# clock.net
KiCad netlist of a schematic drawn in Altium Designer
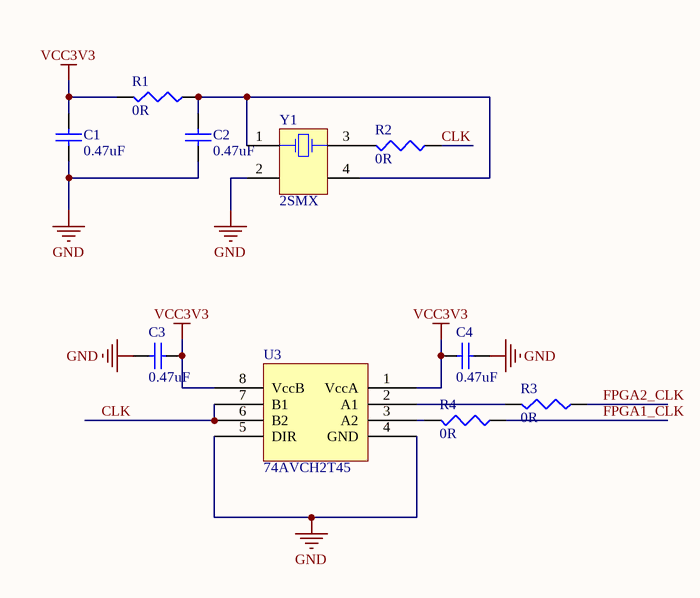
[diagram p0: clock.SchDoc]

(export (version "E")
  (design (tool "Eeschema 10.0.6"))
  (components
    (comp (ref "C1")
      (value "0.47uF")
      (footprint "CAPC1005N")
      (description "Capacitor (Semiconductor SIM Model)")
      (fields (field (name "PUBLISHER") "Altium Limited"))
      (libsource (lib "Miscellaneous Devices") (part "Cap Semi"))
    )
    (comp (ref "C2")
      (value "0.47uF")
      (footprint "CAPC1005N")
      (description "Capacitor (Semiconductor SIM Model)")
      (fields (field (name "PUBLISHER") "Altium Limited"))
      (libsource (lib "Miscellaneous Devices") (part "Cap Semi"))
    )
    (comp (ref "C3")
      (value "0.47uF")
      (footprint "CAPC1005N")
      (description "Capacitor (Semiconductor SIM Model)")
      (fields (field (name "PUBLISHER") "Altium Limited"))
      (libsource (lib "Miscellaneous Devices") (part "Cap Semi"))
    )
    (comp (ref "C4")
      (value "0.47uF")
      (footprint "CAPC1005N")
      (description "Capacitor (Semiconductor SIM Model)")
      (fields (field (name "PUBLISHER") "Altium Limited"))
      (libsource (lib "Miscellaneous Devices") (part "Cap Semi"))
    )
    (comp (ref "R1")
      (value "0R")
      (footprint "RESC1005N")
      (description "Resistor")
      (fields (field (name "PUBLISHER") "Altium Limited"))
      (libsource (lib "Miscellaneous Devices") (part "Res3"))
    )
    (comp (ref "R2")
      (value "0R")
      (footprint "RESC1005N")
      (description "Resistor")
      (fields (field (name "PUBLISHER") "Altium Limited"))
      (libsource (lib "Miscellaneous Devices") (part "Res3"))
    )
    (comp (ref "R3")
      (value "0R")
      (footprint "RESC1005N")
      (description "Resistor")
      (fields (field (name "PUBLISHER") "Altium Limited"))
      (libsource (lib "Miscellaneous Devices") (part "Res3"))
    )
    (comp (ref "R4")
      (value "0R")
      (footprint "RESC1005N")
      (description "Resistor")
      (fields (field (name "PUBLISHER") "Altium Limited"))
      (libsource (lib "Miscellaneous Devices") (part "Res3"))
    )
    (comp (ref "U3") (value "74AVCH2T45") (footprint "SOT765-1") (libsource (lib "S6") (part "74AVCH2T45")))
    (comp (ref "Y1")
      (value "2SMX")
      (footprint "SMX2")
      (description "Surface Mount Quartz Crystal")
      (fields (field (name "PUBLISHER") "Altium Limited"))
      (libsource (lib "C-MAC Crystal Oscillator") (part "2SMX"))
    )
  )
  (nets
    (net (code "1") (name "/CLK") (class "Default")
      (node (ref "R2") (pin "1") (pinfunction "1_1") (pintype "passive"))
      (node (ref "U3") (pin "6") (pinfunction "B2_6") (pintype "passive"))
      (node (ref "U3") (pin "7") (pinfunction "B1_7") (pintype "passive"))
    )
    (net (code "2") (name "/FPGA1_CLK") (class "Default")
      (node (ref "R4") (pin "1") (pinfunction "1_1") (pintype "passive"))
    )
    (net (code "3") (name "/FPGA2_CLK") (class "Default")
      (node (ref "R3") (pin "1") (pinfunction "1_1") (pintype "passive"))
    )
    (net (code "4") (name "GND") (class "Default")
      (node (ref "C1") (pin "1") (pinfunction "1_1") (pintype "passive"))
      (node (ref "C2") (pin "1") (pinfunction "1_1") (pintype "passive"))
      (node (ref "C3") (pin "2") (pinfunction "2_2") (pintype "passive"))
      (node (ref "C4") (pin "1") (pinfunction "1_1") (pintype "passive"))
      (node (ref "U3") (pin "4") (pinfunction "GND_4") (pintype "passive"))
      (node (ref "U3") (pin "5") (pinfunction "DIR_5") (pintype "passive"))
      (node (ref "Y1") (pin "2") (pinfunction "NC_2") (pintype "passive"))
    )
    (net (code "5") (name "Net-(U3-A1)") (class "Default")
      (node (ref "R3") (pin "2") (pinfunction "2_2") (pintype "passive"))
      (node (ref "U3") (pin "2") (pinfunction "A1_2") (pintype "passive"))
    )
    (net (code "6") (name "Net-(U3-A2)") (class "Default")
      (node (ref "R4") (pin "2") (pinfunction "2_2") (pintype "passive"))
      (node (ref "U3") (pin "3") (pinfunction "A2_3") (pintype "passive"))
    )
    (net (code "7") (name "Net-(Y1-OSC1)") (class "Default")
      (node (ref "C2") (pin "2") (pinfunction "2_2") (pintype "passive"))
      (node (ref "R1") (pin "1") (pinfunction "1_1") (pintype "passive"))
      (node (ref "Y1") (pin "1") (pinfunction "OSC1_1") (pintype "passive"))
      (node (ref "Y1") (pin "4") (pinfunction "NC_4") (pintype "passive"))
    )
    (net (code "8") (name "Net-(Y1-OSC2)") (class "Default")
      (node (ref "R2") (pin "2") (pinfunction "2_2") (pintype "passive"))
      (node (ref "Y1") (pin "3") (pinfunction "OSC2_3") (pintype "passive"))
    )
    (net (code "9") (name "VCC3V3") (class "Default")
      (node (ref "C1") (pin "2") (pinfunction "2_2") (pintype "passive"))
      (node (ref "C3") (pin "1") (pinfunction "1_1") (pintype "passive"))
      (node (ref "C4") (pin "2") (pinfunction "2_2") (pintype "passive"))
      (node (ref "R1") (pin "2") (pinfunction "2_2") (pintype "passive"))
      (node (ref "U3") (pin "1") (pinfunction "VccA_1") (pintype "passive"))
      (node (ref "U3") (pin "8") (pinfunction "VccB_8") (pintype "passive"))
    )
  )
)
